# simplified_auv_power_layout_v1_0.net
KiCad netlist of a schematic drawn in EAGLE
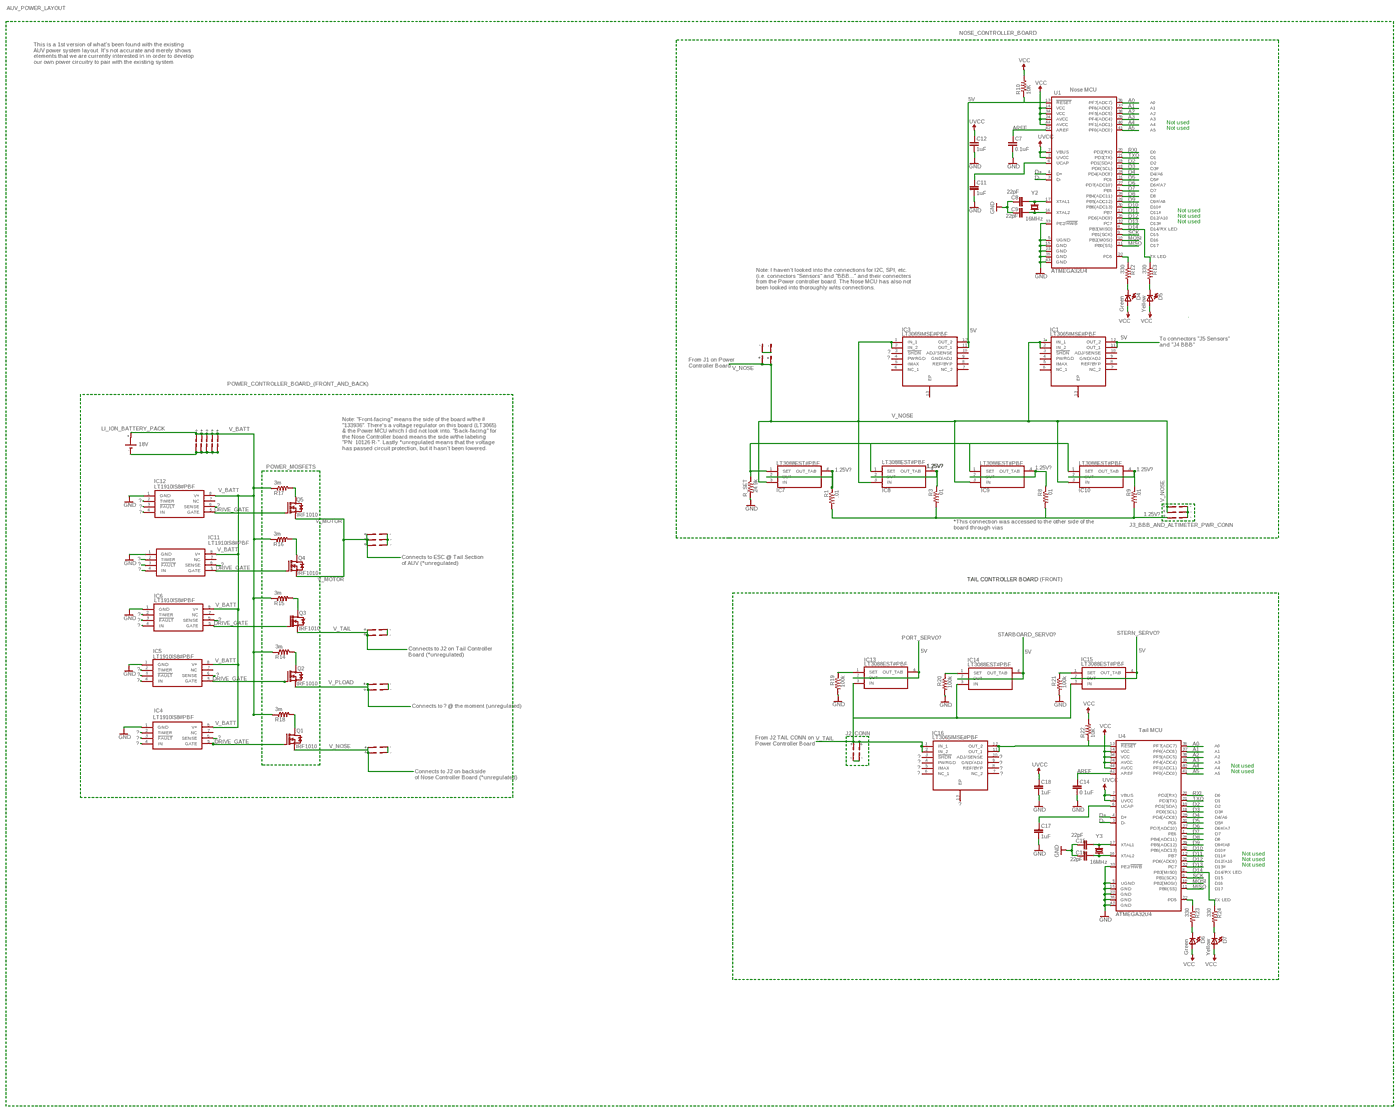
[diagram p0: schematic, sheet 1, overview]
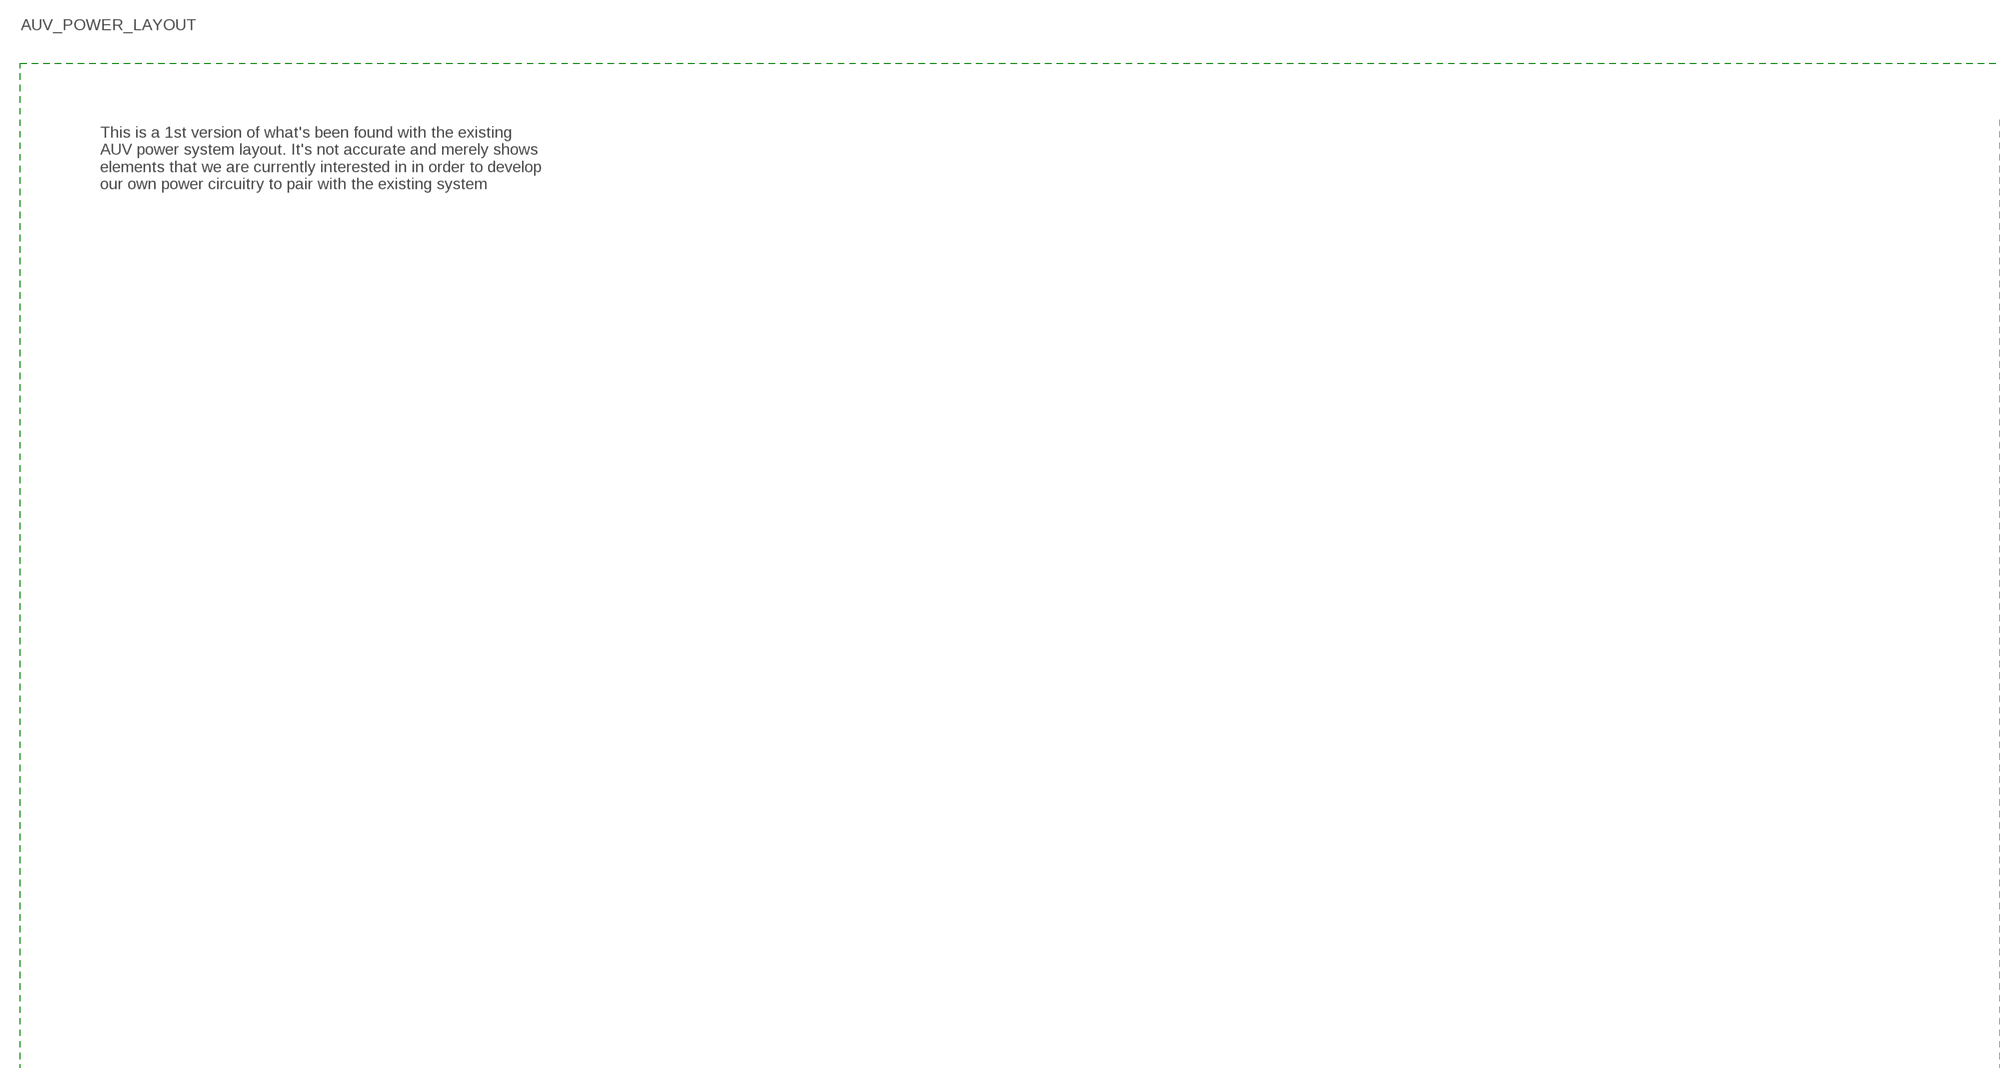
[diagram p1: schematic, sheet 1, part 1 of 4]
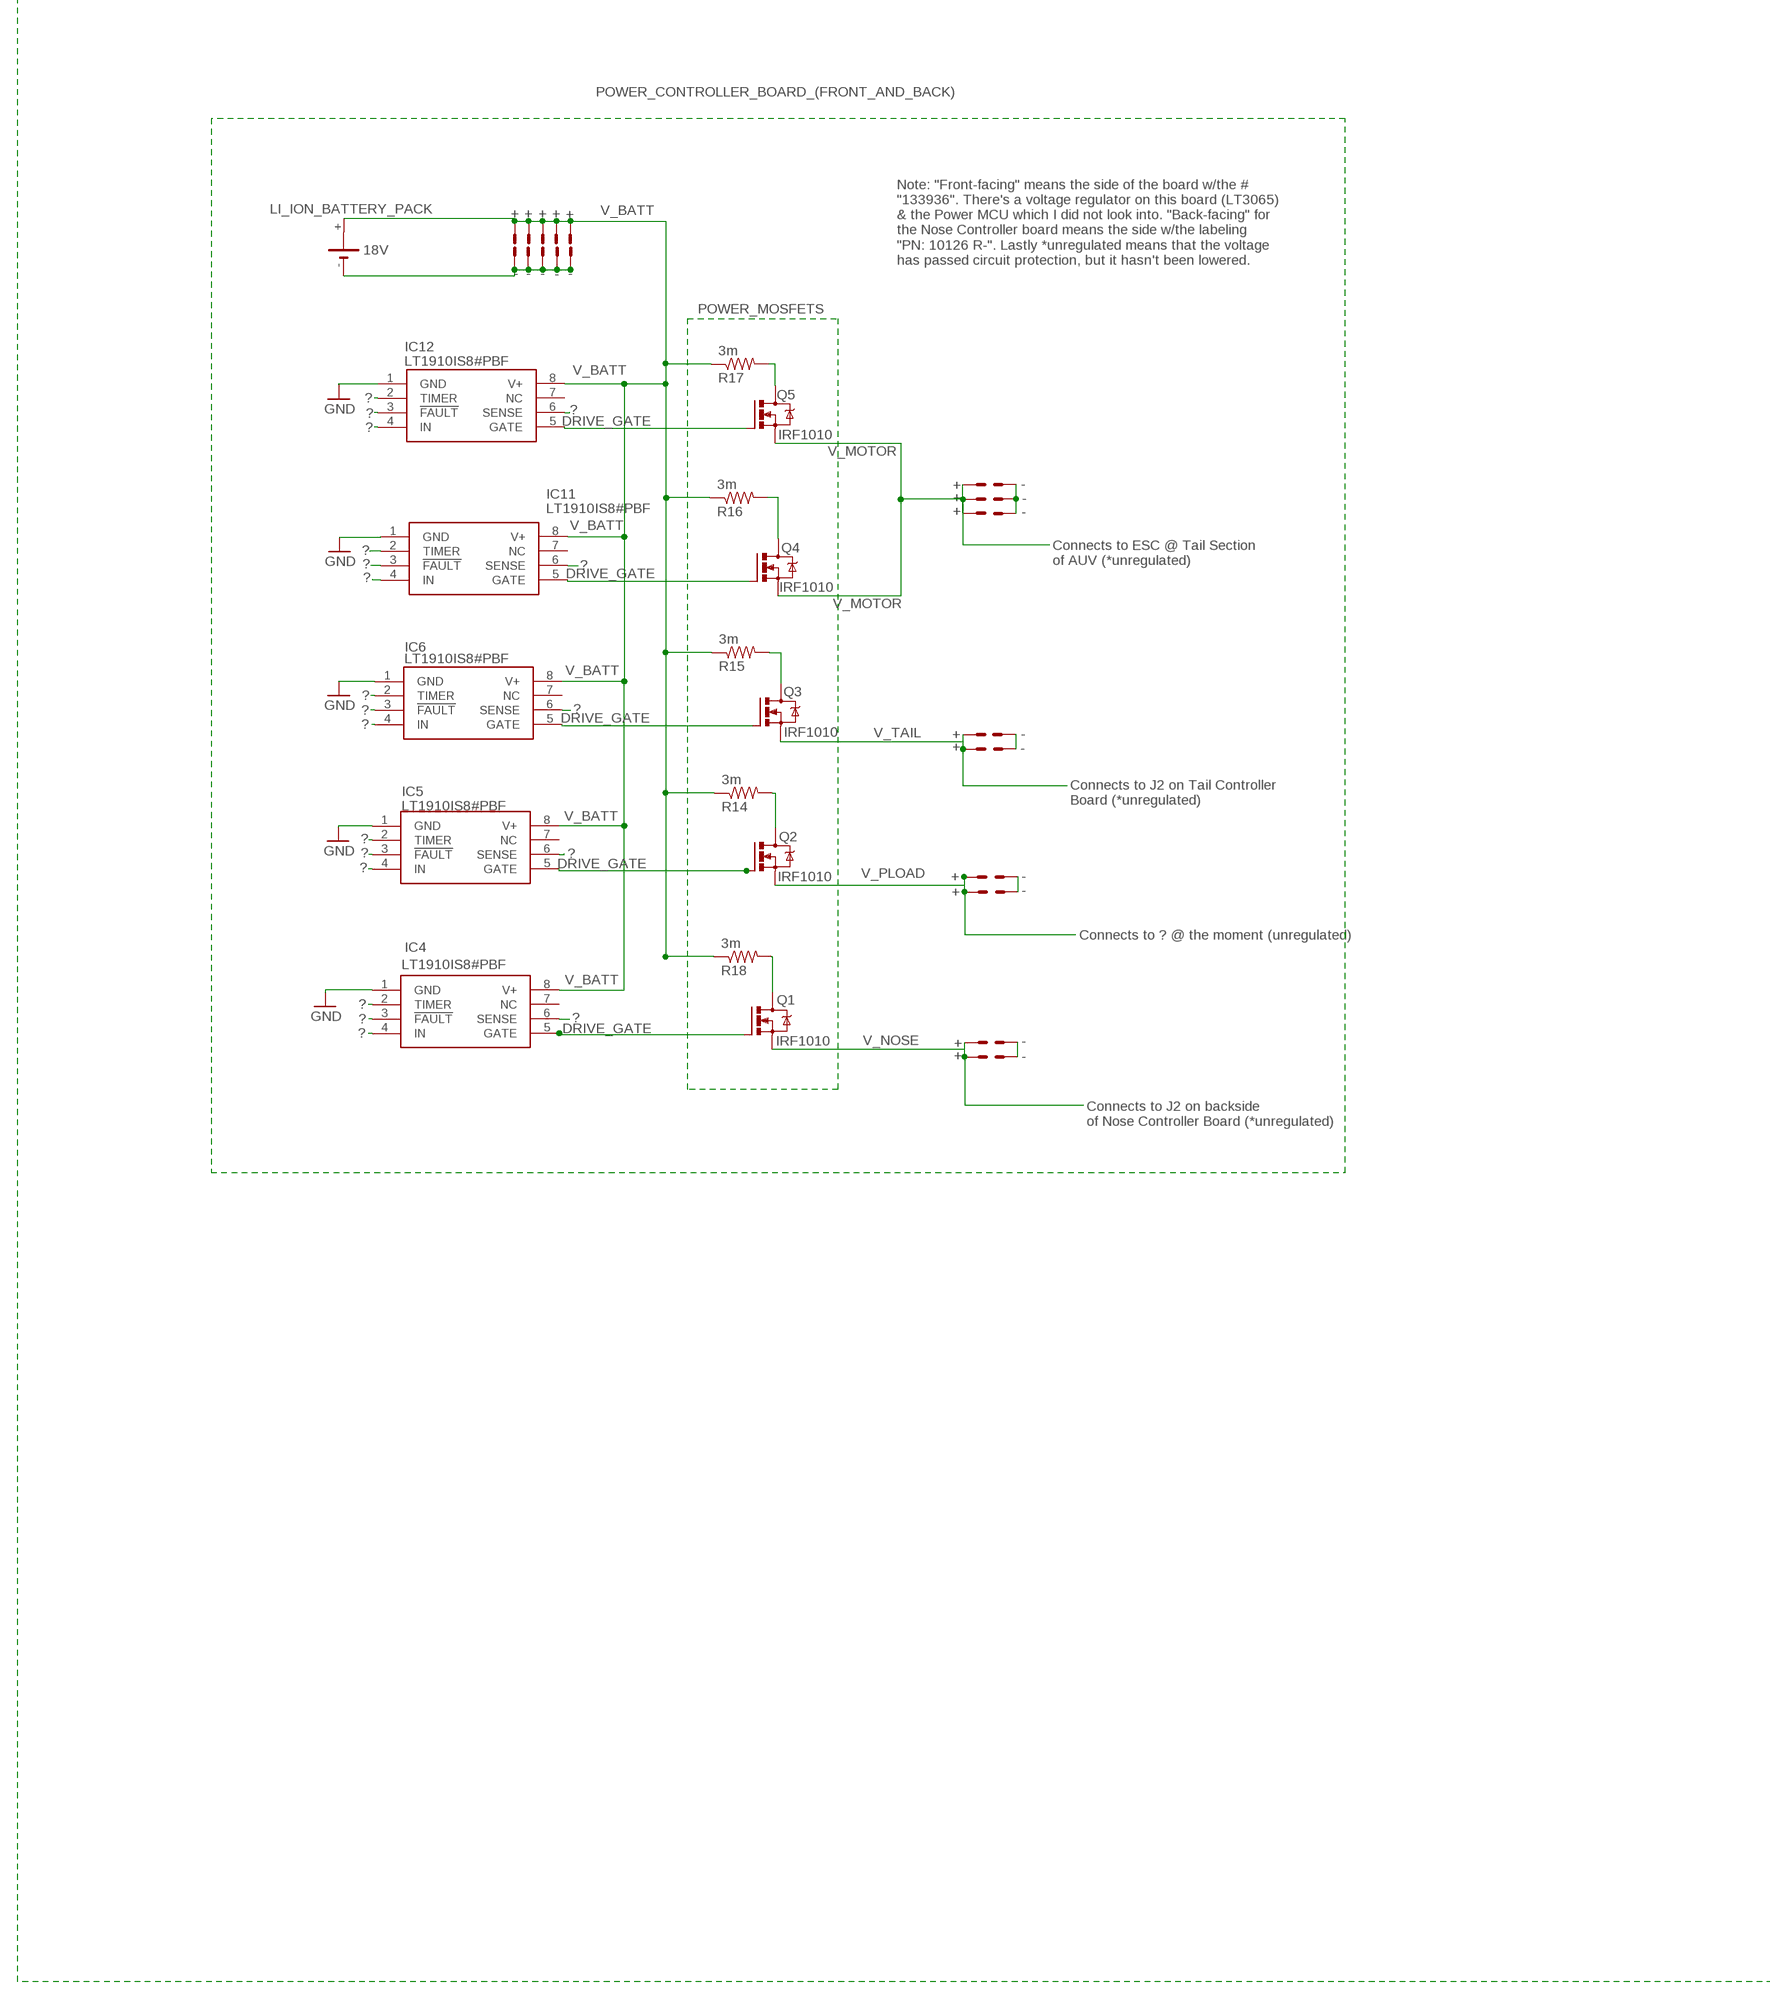
[diagram p2: schematic, sheet 1, part 2 of 4]
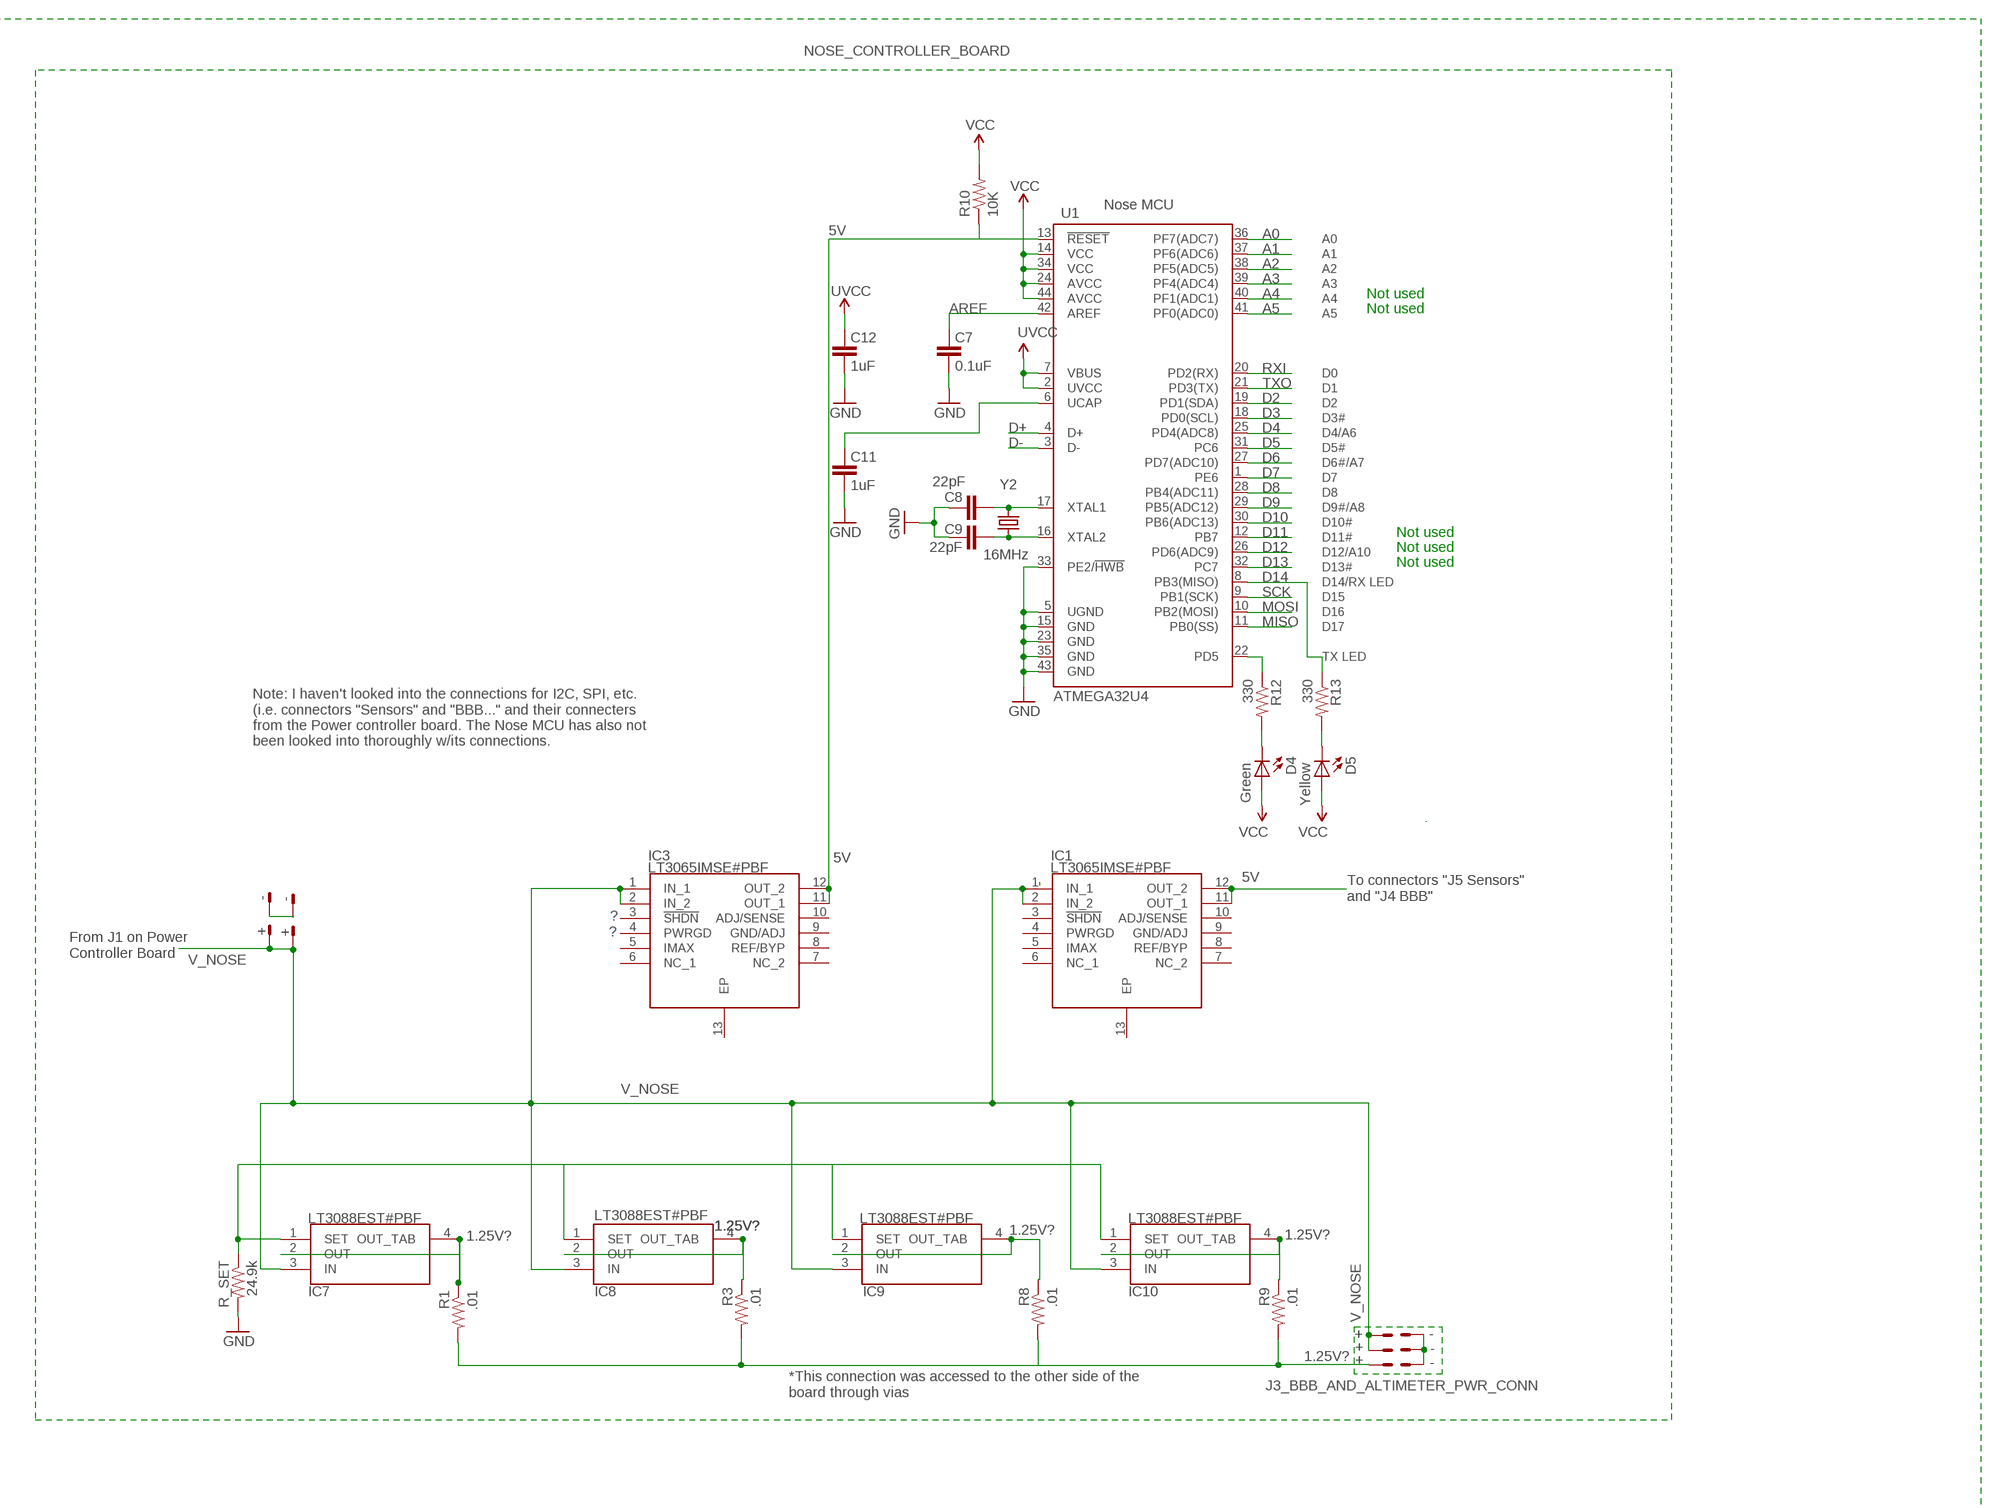
[diagram p3: schematic, sheet 1, part 3 of 4]
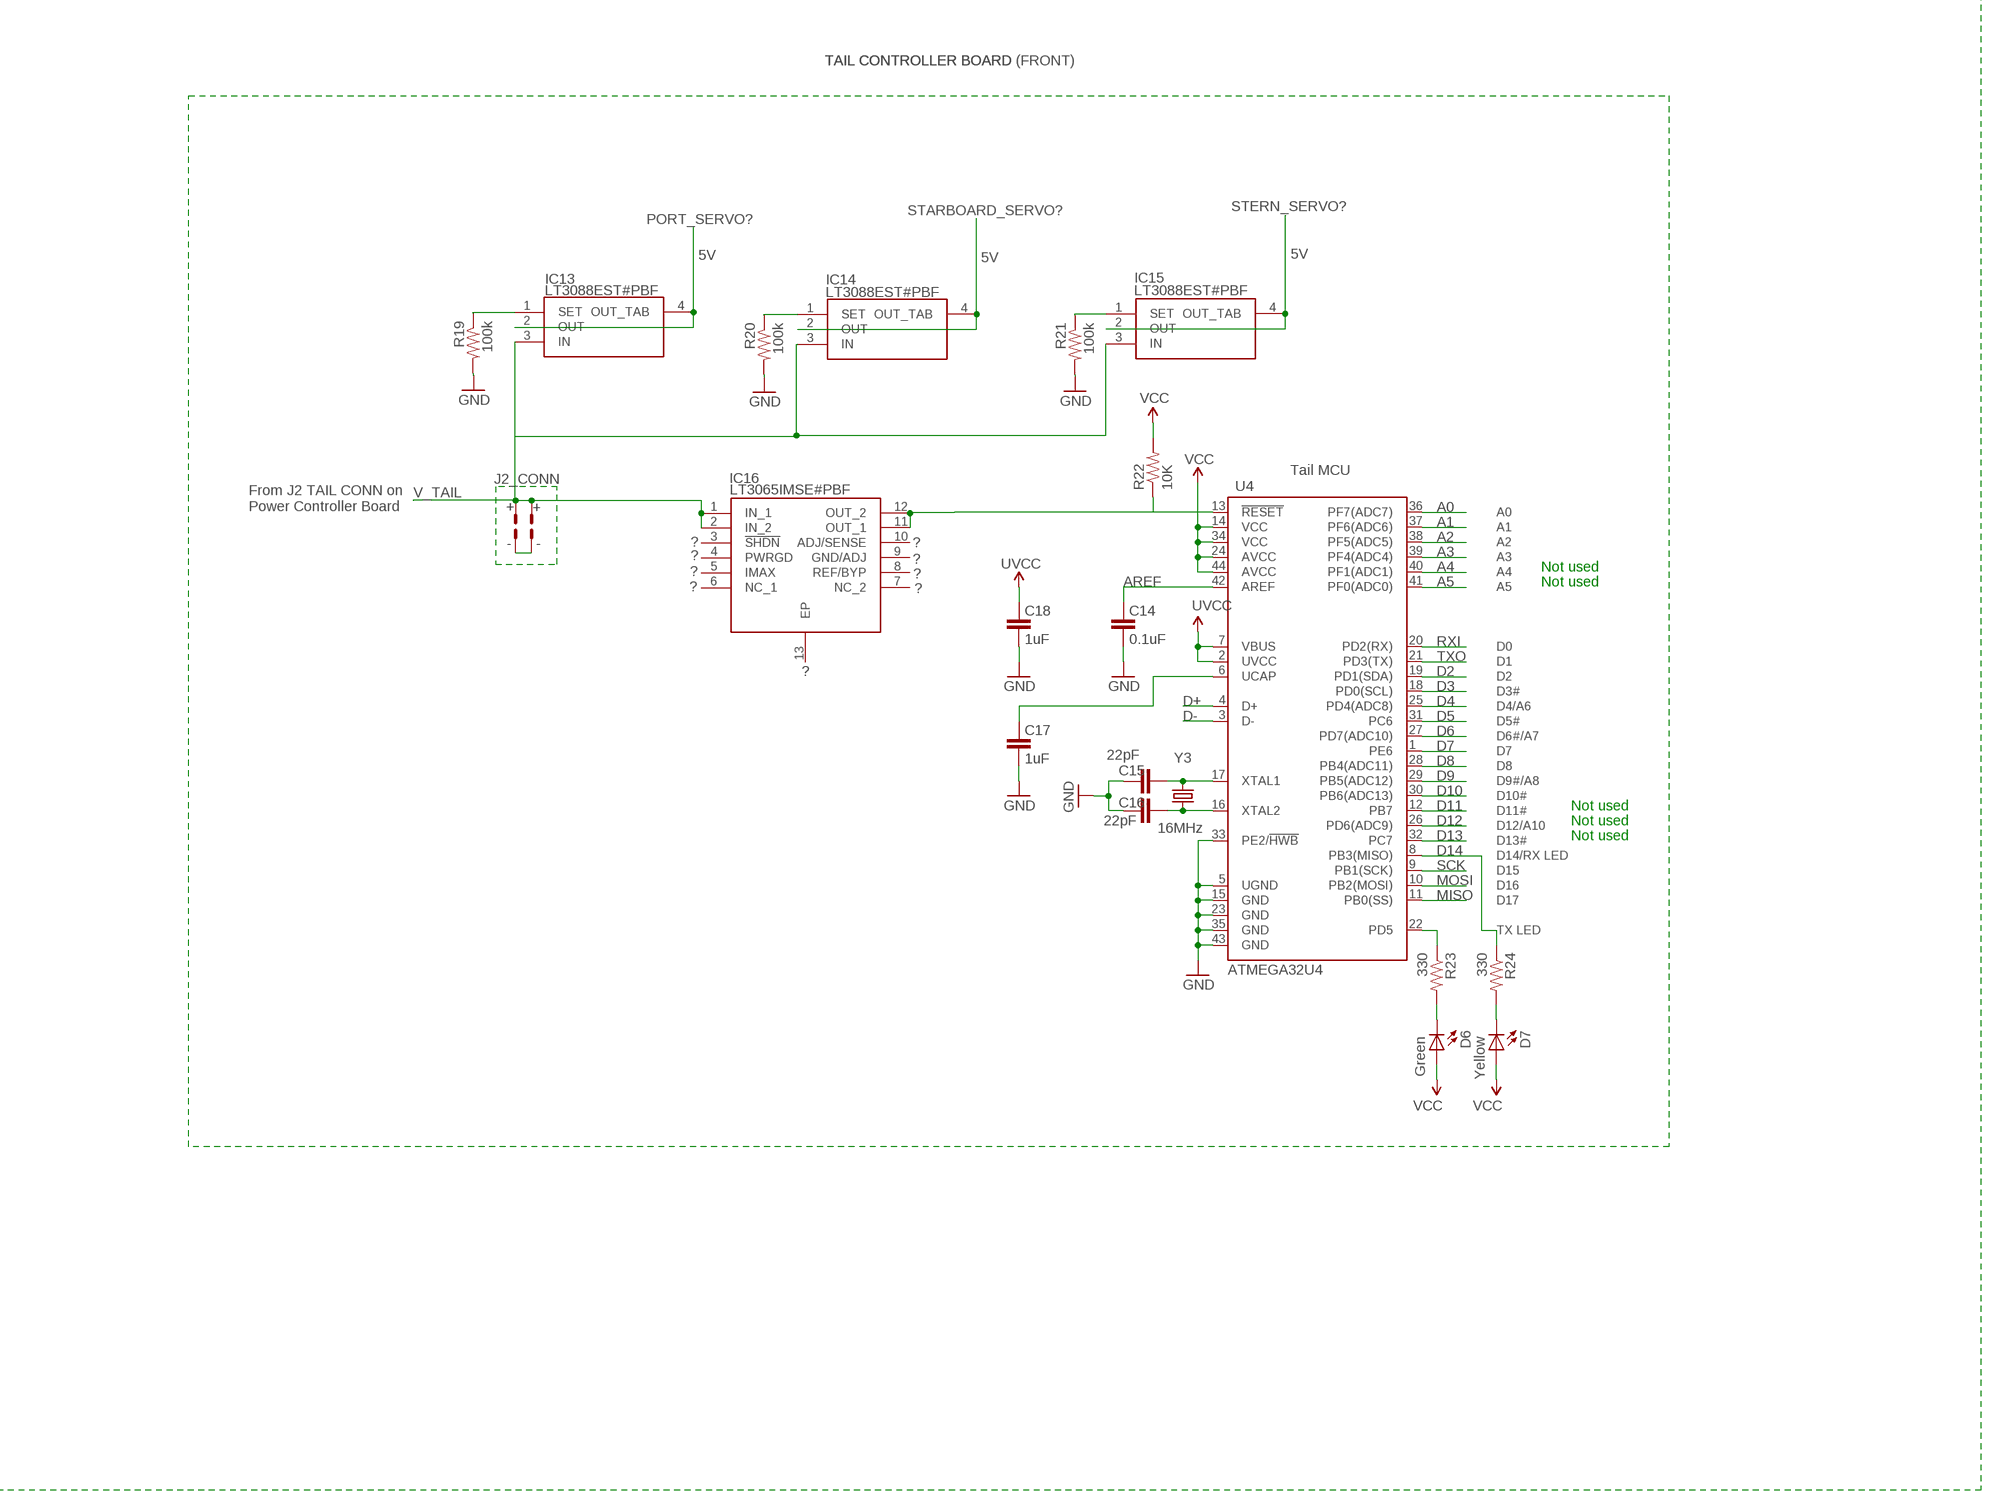
[diagram p4: schematic, sheet 1, part 4 of 4]

(export (version "E")
  (design (tool "Eeschema 10.0.6"))
  (components
    (comp (ref "C7")
      (value "0.1uF")
      (footprint "eagle-import:0603-CAP")
      (libsource (lib "eagle-import") (part "CAP0603-CAP"))
    )
    (comp (ref "C8")
      (value "22pF")
      (footprint "eagle-import:0603-CAP")
      (libsource (lib "eagle-import") (part "CAP0603-CAP"))
    )
    (comp (ref "C9")
      (value "22pF")
      (footprint "eagle-import:0603-CAP")
      (libsource (lib "eagle-import") (part "CAP0603-CAP"))
    )
    (comp (ref "C11")
      (value "1uF")
      (footprint "eagle-import:0603-CAP")
      (libsource (lib "eagle-import") (part "CAP0603-CAP"))
    )
    (comp (ref "C12")
      (value "1uF")
      (footprint "eagle-import:0603-CAP")
      (libsource (lib "eagle-import") (part "CAP0603-CAP"))
    )
    (comp (ref "C14")
      (value "0.1uF")
      (footprint "eagle-import:0603-CAP")
      (libsource (lib "eagle-import") (part "CAP0603-CAP"))
    )
    (comp (ref "C15")
      (value "22pF")
      (footprint "eagle-import:0603-CAP")
      (libsource (lib "eagle-import") (part "CAP0603-CAP"))
    )
    (comp (ref "C16")
      (value "22pF")
      (footprint "eagle-import:0603-CAP")
      (libsource (lib "eagle-import") (part "CAP0603-CAP"))
    )
    (comp (ref "C17")
      (value "1uF")
      (footprint "eagle-import:0603-CAP")
      (libsource (lib "eagle-import") (part "CAP0603-CAP"))
    )
    (comp (ref "C18")
      (value "1uF")
      (footprint "eagle-import:0603-CAP")
      (libsource (lib "eagle-import") (part "CAP0603-CAP"))
    )
    (comp (ref "D4")
      (value "Green")
      (footprint "eagle-import:LED-0603")
      (libsource (lib "eagle-import") (part "LED0603"))
    )
    (comp (ref "D5")
      (value "Yellow")
      (footprint "eagle-import:LED-0603")
      (libsource (lib "eagle-import") (part "LED0603"))
    )
    (comp (ref "D6")
      (value "Green")
      (footprint "eagle-import:LED-0603")
      (libsource (lib "eagle-import") (part "LED0603"))
    )
    (comp (ref "D7")
      (value "Yellow")
      (footprint "eagle-import:LED-0603")
      (libsource (lib "eagle-import") (part "LED0603"))
    )
    (comp (ref "IC1")
      (value "LT3065IMSE#PBF")
      (footprint "eagle-import:SOP65P490X110-13N")
      (fields (field (name "MOUSER_PART_NUMBER") "584-LT3065IMSE#PBF"))
      (libsource (lib "eagle-import") (part "LT3065IMSE#PBF"))
    )
    (comp (ref "IC3")
      (value "LT3065IMSE#PBF")
      (footprint "eagle-import:SOP65P490X110-13N")
      (fields (field (name "MOUSER_PART_NUMBER") "584-LT3065IMSE#PBF"))
      (libsource (lib "eagle-import") (part "LT3065IMSE#PBF"))
    )
    (comp (ref "IC4")
      (value "LT1910IS8#PBF")
      (footprint "eagle-import:SOIC127P599X175-8N")
      (fields
        (field (name "MOUSER_PART_NUMBER") "584-LT1910IS8#PBF")
        (field (name "RS_PART_NUMBER") "7799502")
      )
      (libsource (lib "eagle-import") (part "LT1910IS8#PBF"))
    )
    (comp (ref "IC5")
      (value "LT1910IS8#PBF")
      (footprint "eagle-import:SOIC127P599X175-8N")
      (fields
        (field (name "MOUSER_PART_NUMBER") "584-LT1910IS8#PBF")
        (field (name "RS_PART_NUMBER") "7799502")
      )
      (libsource (lib "eagle-import") (part "LT1910IS8#PBF"))
    )
    (comp (ref "IC6")
      (value "LT1910IS8#PBF")
      (footprint "eagle-import:SOIC127P599X175-8N")
      (fields
        (field (name "MOUSER_PART_NUMBER") "584-LT1910IS8#PBF")
        (field (name "RS_PART_NUMBER") "7799502")
      )
      (libsource (lib "eagle-import") (part "LT1910IS8#PBF"))
    )
    (comp (ref "IC7")
      (value "LT3088EST#PBF")
      (footprint "eagle-import:SOT230P700X180-4N")
      (fields (field (name "MOUSER_PART_NUMBER") "584-LT3088EST#PBF"))
      (libsource (lib "eagle-import") (part "LT3088EST#PBF"))
    )
    (comp (ref "IC8")
      (value "LT3088EST#PBF")
      (footprint "eagle-import:SOT230P700X180-4N")
      (fields (field (name "MOUSER_PART_NUMBER") "584-LT3088EST#PBF"))
      (libsource (lib "eagle-import") (part "LT3088EST#PBF"))
    )
    (comp (ref "IC9")
      (value "LT3088EST#PBF")
      (footprint "eagle-import:SOT230P700X180-4N")
      (fields (field (name "MOUSER_PART_NUMBER") "584-LT3088EST#PBF"))
      (libsource (lib "eagle-import") (part "LT3088EST#PBF"))
    )
    (comp (ref "IC10")
      (value "LT3088EST#PBF")
      (footprint "eagle-import:SOT230P700X180-4N")
      (fields (field (name "MOUSER_PART_NUMBER") "584-LT3088EST#PBF"))
      (libsource (lib "eagle-import") (part "LT3088EST#PBF"))
    )
    (comp (ref "IC11")
      (value "LT1910IS8#PBF")
      (footprint "eagle-import:SOIC127P599X175-8N")
      (fields
        (field (name "MOUSER_PART_NUMBER") "584-LT1910IS8#PBF")
        (field (name "RS_PART_NUMBER") "7799502")
      )
      (libsource (lib "eagle-import") (part "LT1910IS8#PBF"))
    )
    (comp (ref "IC12")
      (value "LT1910IS8#PBF")
      (footprint "eagle-import:SOIC127P599X175-8N")
      (fields
        (field (name "MOUSER_PART_NUMBER") "584-LT1910IS8#PBF")
        (field (name "RS_PART_NUMBER") "7799502")
      )
      (libsource (lib "eagle-import") (part "LT1910IS8#PBF"))
    )
    (comp (ref "IC13")
      (value "LT3088EST#PBF")
      (footprint "eagle-import:SOT230P700X180-4N")
      (fields (field (name "MOUSER_PART_NUMBER") "584-LT3088EST#PBF"))
      (libsource (lib "eagle-import") (part "LT3088EST#PBF"))
    )
    (comp (ref "IC14")
      (value "LT3088EST#PBF")
      (footprint "eagle-import:SOT230P700X180-4N")
      (fields (field (name "MOUSER_PART_NUMBER") "584-LT3088EST#PBF"))
      (libsource (lib "eagle-import") (part "LT3088EST#PBF"))
    )
    (comp (ref "IC15")
      (value "LT3088EST#PBF")
      (footprint "eagle-import:SOT230P700X180-4N")
      (fields (field (name "MOUSER_PART_NUMBER") "584-LT3088EST#PBF"))
      (libsource (lib "eagle-import") (part "LT3088EST#PBF"))
    )
    (comp (ref "IC16")
      (value "LT3065IMSE#PBF")
      (footprint "eagle-import:SOP65P490X110-13N")
      (fields (field (name "MOUSER_PART_NUMBER") "584-LT3065IMSE#PBF"))
      (libsource (lib "eagle-import") (part "LT3065IMSE#PBF"))
    )
    (comp (ref "J4_BATTERY_CONNECTOR")
      (value "J4_BATTERY")
      (footprint "eagle-import:5566-10")
      (fields (field (name "MF") "MOLEX"))
      (libsource (lib "eagle-import") (part "5566-10"))
    )
    (comp (ref "LI_ION_BATTERY_PACK")
      (value "18V")
      (footprint "eagle-import:CR2032H")
      (libsource (lib "eagle-import") (part "CR2032H"))
    )
    (comp (ref "Q1")
      (value "IRF1010")
      (footprint "eagle-import:TO220BV")
      (libsource (lib "eagle-import") (part "IRF540"))
    )
    (comp (ref "Q2")
      (value "IRF1010")
      (footprint "eagle-import:TO220BV")
      (libsource (lib "eagle-import") (part "IRF540"))
    )
    (comp (ref "Q3")
      (value "IRF1010")
      (footprint "eagle-import:TO220BV")
      (libsource (lib "eagle-import") (part "IRF540"))
    )
    (comp (ref "Q4")
      (value "IRF1010")
      (footprint "eagle-import:TO220BV")
      (libsource (lib "eagle-import") (part "IRF540"))
    )
    (comp (ref "Q5")
      (value "IRF1010")
      (footprint "eagle-import:TO220BV")
      (libsource (lib "eagle-import") (part "IRF540"))
    )
    (comp (ref "R1")
      (value ".01")
      (footprint "eagle-import:0414V")
      (libsource (lib "eagle-import") (part "R-US_0414/5V"))
    )
    (comp (ref "R3")
      (value ".01")
      (footprint "eagle-import:0414V")
      (libsource (lib "eagle-import") (part "R-US_0414/5V"))
    )
    (comp (ref "R8")
      (value ".01")
      (footprint "eagle-import:0414V")
      (libsource (lib "eagle-import") (part "R-US_0414/5V"))
    )
    (comp (ref "R9")
      (value ".01")
      (footprint "eagle-import:0414V")
      (libsource (lib "eagle-import") (part "R-US_0414/5V"))
    )
    (comp (ref "R10")
      (value "10K")
      (footprint "eagle-import:0603-RES")
      (libsource (lib "eagle-import") (part "RESISTOR0603-RES"))
    )
    (comp (ref "R12")
      (value "330")
      (footprint "eagle-import:0603-RES")
      (libsource (lib "eagle-import") (part "RESISTOR0603-RES"))
    )
    (comp (ref "R13")
      (value "330")
      (footprint "eagle-import:0603-RES")
      (libsource (lib "eagle-import") (part "RESISTOR0603-RES"))
    )
    (comp (ref "R14")
      (value "3m")
      (footprint "eagle-import:0414V")
      (libsource (lib "eagle-import") (part "R-US_0414/5V"))
    )
    (comp (ref "R15")
      (value "3m")
      (footprint "eagle-import:0414V")
      (libsource (lib "eagle-import") (part "R-US_0414/5V"))
    )
    (comp (ref "R16")
      (value "3m")
      (footprint "eagle-import:0414V")
      (libsource (lib "eagle-import") (part "R-US_0414/5V"))
    )
    (comp (ref "R17")
      (value "3m")
      (footprint "eagle-import:0414V")
      (libsource (lib "eagle-import") (part "R-US_0414/5V"))
    )
    (comp (ref "R18")
      (value "3m")
      (footprint "eagle-import:0414V")
      (libsource (lib "eagle-import") (part "R-US_0414/5V"))
    )
    (comp (ref "R19")
      (value "100k")
      (footprint "eagle-import:0414V")
      (libsource (lib "eagle-import") (part "R-US_0414/5V"))
    )
    (comp (ref "R20")
      (value "100k")
      (footprint "eagle-import:0414V")
      (libsource (lib "eagle-import") (part "R-US_0414/5V"))
    )
    (comp (ref "R21")
      (value "100k")
      (footprint "eagle-import:0414V")
      (libsource (lib "eagle-import") (part "R-US_0414/5V"))
    )
    (comp (ref "R22")
      (value "10K")
      (footprint "eagle-import:0603-RES")
      (libsource (lib "eagle-import") (part "RESISTOR0603-RES"))
    )
    (comp (ref "R23")
      (value "330")
      (footprint "eagle-import:0603-RES")
      (libsource (lib "eagle-import") (part "RESISTOR0603-RES"))
    )
    (comp (ref "R24")
      (value "330")
      (footprint "eagle-import:0603-RES")
      (libsource (lib "eagle-import") (part "RESISTOR0603-RES"))
    )
    (comp (ref "R_SET")
      (value "24.9k")
      (footprint "eagle-import:0414V")
      (libsource (lib "eagle-import") (part "R-US_0414/5V"))
    )
    (comp (ref "U1")
      (value "ATMEGA32U4")
      (footprint "eagle-import:QFN-44-NOPAD_1_1-OUTFAKES")
      (libsource (lib "eagle-import") (part "ATMEGA32U4OUTFAKES"))
    )
    (comp (ref "U4")
      (value "ATMEGA32U4")
      (footprint "eagle-import:QFN-44-NOPAD_1_1-OUTFAKES")
      (libsource (lib "eagle-import") (part "ATMEGA32U4OUTFAKES"))
    )
    (comp (ref "X3")
      (value "-")
      (footprint "eagle-import:87758-0216")
      (fields (field (name "MF") "MOLEX") (field (name "MPN") "87758-0216"))
      (libsource (lib "eagle-import") (part "87758-0216"))
    )
    (comp (ref "X4")
      (value "+")
      (footprint "eagle-import:87758-0216")
      (fields (field (name "MF") "MOLEX") (field (name "MPN") "87758-0216"))
      (libsource (lib "eagle-import") (part "87758-0216"))
    )
    (comp (ref "X6")
      (value "52746-4")
      (footprint "eagle-import:52746-4")
      (fields (field (name "MF") "MOLEX") (field (name "MPN") "52746-442"))
      (libsource (lib "eagle-import") (part "52746-4"))
    )
    (comp (ref "X7")
      (value "52746-4")
      (footprint "eagle-import:52746-4")
      (fields (field (name "MF") "MOLEX") (field (name "MPN") "52746-442"))
      (libsource (lib "eagle-import") (part "52746-4"))
    )
    (comp (ref "X8")
      (value "52746-4")
      (footprint "eagle-import:52746-4")
      (fields (field (name "MF") "MOLEX") (field (name "MPN") "52746-442"))
      (libsource (lib "eagle-import") (part "52746-4"))
    )
    (comp (ref "X9")
      (value "52746-4")
      (footprint "eagle-import:52746-4")
      (fields (field (name "MF") "MOLEX") (field (name "MPN") "52746-442"))
      (libsource (lib "eagle-import") (part "52746-4"))
    )
    (comp (ref "X10")
      (value "52746-6")
      (footprint "eagle-import:52746-6")
      (fields (field (name "MF") "MOLEX"))
      (libsource (lib "eagle-import") (part "52746-6"))
    )
    (comp (ref "X11")
      (value "52746-6")
      (footprint "eagle-import:52746-6")
      (fields (field (name "MF") "MOLEX"))
      (libsource (lib "eagle-import") (part "52746-6"))
    )
    (comp (ref "Y2")
      (value "16MHz")
      (footprint "eagle-import:CRYSTAL-SMD-5X3")
      (libsource (lib "eagle-import") (part "CRYSTAL5X3"))
    )
    (comp (ref "Y3")
      (value "16MHz")
      (footprint "eagle-import:CRYSTAL-SMD-5X3")
      (libsource (lib "eagle-import") (part "CRYSTAL5X3"))
    )
  )
  (nets
    (net (code "1") (name "/+") (class "Default")
      (node (ref "IC11") (pin "8") (pinfunction "V+_8") (pintype "bidirectional"))
      (node (ref "IC12") (pin "8") (pinfunction "V+_8") (pintype "bidirectional"))
      (node (ref "IC4") (pin "8") (pinfunction "V+_8") (pintype "bidirectional"))
      (node (ref "IC5") (pin "8") (pinfunction "V+_8") (pintype "bidirectional"))
      (node (ref "IC6") (pin "8") (pinfunction "V+_8") (pintype "bidirectional"))
      (node (ref "J4_BATTERY_CONNECTOR") (pin "1") (pinfunction "S_1") (pintype "passive"))
      (node (ref "J4_BATTERY_CONNECTOR") (pin "2") (pinfunction "S_2") (pintype "passive"))
      (node (ref "J4_BATTERY_CONNECTOR") (pin "3") (pinfunction "S_3") (pintype "passive"))
      (node (ref "J4_BATTERY_CONNECTOR") (pin "4") (pinfunction "S_4") (pintype "passive"))
      (node (ref "J4_BATTERY_CONNECTOR") (pin "5") (pinfunction "S_5") (pintype "passive"))
      (node (ref "LI_ION_BATTERY_PACK") (pin "+") (pinfunction "+_+") (pintype "passive"))
      (node (ref "R14") (pin "1") (pinfunction "1_1") (pintype "passive"))
      (node (ref "R15") (pin "1") (pinfunction "1_1") (pintype "passive"))
      (node (ref "R16") (pin "1") (pinfunction "1_1") (pintype "passive"))
      (node (ref "R17") (pin "1") (pinfunction "1_1") (pintype "passive"))
      (node (ref "R18") (pin "1") (pinfunction "1_1") (pintype "passive"))
    )
    (net (code "2") (name "/-") (class "Default")
      (node (ref "J4_BATTERY_CONNECTOR") (pin "10") (pinfunction "S_10") (pintype "passive"))
      (node (ref "J4_BATTERY_CONNECTOR") (pin "6") (pinfunction "S_6") (pintype "passive"))
      (node (ref "J4_BATTERY_CONNECTOR") (pin "7") (pinfunction "S_7") (pintype "passive"))
      (node (ref "J4_BATTERY_CONNECTOR") (pin "8") (pinfunction "S_8") (pintype "passive"))
      (node (ref "J4_BATTERY_CONNECTOR") (pin "9") (pinfunction "S_9") (pintype "passive"))
      (node (ref "LI_ION_BATTERY_PACK") (pin "-") (pinfunction "-_-") (pintype "passive"))
    )
    (net (code "3") (name "/1.25V?") (class "Default")
      (node (ref "IC10") (pin "2") (pinfunction "OUT_2") (pintype "output"))
      (node (ref "IC10") (pin "4") (pinfunction "OUT_TAB_4") (pintype "output"))
      (node (ref "IC7") (pin "2") (pinfunction "OUT_2") (pintype "output"))
      (node (ref "IC7") (pin "4") (pinfunction "OUT_TAB_4") (pintype "output"))
      (node (ref "IC8") (pin "2") (pinfunction "OUT_2") (pintype "output"))
      (node (ref "IC8") (pin "4") (pinfunction "OUT_TAB_4") (pintype "output"))
      (node (ref "IC9") (pin "2") (pinfunction "OUT_2") (pintype "output"))
      (node (ref "IC9") (pin "4") (pinfunction "OUT_TAB_4") (pintype "output"))
      (node (ref "R1") (pin "1") (pinfunction "1_1") (pintype "passive"))
      (node (ref "R3") (pin "1") (pinfunction "1_1") (pintype "passive"))
      (node (ref "R8") (pin "1") (pinfunction "1_1") (pintype "passive"))
      (node (ref "R9") (pin "1") (pinfunction "1_1") (pintype "passive"))
    )
    (net (code "4") (name "/?") (class "Default")
      (node (ref "IC11") (pin "2") (pinfunction "TIMER_2") (pintype "bidirectional"))
    )
    (net (code "5") (name "/A0") (class "Default")
      (node (ref "U1") (pin "36") (pinfunction "PF7(ADC7)_36") (pintype "bidirectional"))
      (node (ref "U4") (pin "36") (pinfunction "PF7(ADC7)_36") (pintype "bidirectional"))
    )
    (net (code "6") (name "/A1") (class "Default")
      (node (ref "U1") (pin "37") (pinfunction "PF6(ADC6)_37") (pintype "bidirectional"))
      (node (ref "U4") (pin "37") (pinfunction "PF6(ADC6)_37") (pintype "bidirectional"))
    )
    (net (code "7") (name "/A2") (class "Default")
      (node (ref "U1") (pin "38") (pinfunction "PF5(ADC5)_38") (pintype "bidirectional"))
      (node (ref "U4") (pin "38") (pinfunction "PF5(ADC5)_38") (pintype "bidirectional"))
    )
    (net (code "8") (name "/A3") (class "Default")
      (node (ref "U1") (pin "39") (pinfunction "PF4(ADC4)_39") (pintype "bidirectional"))
      (node (ref "U4") (pin "39") (pinfunction "PF4(ADC4)_39") (pintype "bidirectional"))
    )
    (net (code "9") (name "/A4") (class "Default")
      (node (ref "U1") (pin "40") (pinfunction "PF1(ADC1)_40") (pintype "bidirectional"))
      (node (ref "U4") (pin "40") (pinfunction "PF1(ADC1)_40") (pintype "bidirectional"))
    )
    (net (code "10") (name "/A5") (class "Default")
      (node (ref "U1") (pin "41") (pinfunction "PF0(ADC0)_41") (pintype "bidirectional"))
      (node (ref "U4") (pin "41") (pinfunction "PF0(ADC0)_41") (pintype "bidirectional"))
    )
    (net (code "11") (name "/AREF") (class "Default")
      (node (ref "C14") (pin "2") (pinfunction "2_2") (pintype "passive"))
      (node (ref "C7") (pin "2") (pinfunction "2_2") (pintype "passive"))
      (node (ref "U1") (pin "42") (pinfunction "AREF_42") (pintype "bidirectional"))
      (node (ref "U4") (pin "42") (pinfunction "AREF_42") (pintype "bidirectional"))
    )
    (net (code "13") (name "/D+") (class "Default")
      (node (ref "U1") (pin "4") (pinfunction "D+_4") (pintype "bidirectional"))
      (node (ref "U4") (pin "4") (pinfunction "D+_4") (pintype "bidirectional"))
    )
    (net (code "14") (name "/D-") (class "Default")
      (node (ref "U1") (pin "3") (pinfunction "D-_3") (pintype "bidirectional"))
      (node (ref "U4") (pin "3") (pinfunction "D-_3") (pintype "bidirectional"))
    )
    (net (code "15") (name "/D2") (class "Default")
      (node (ref "U1") (pin "19") (pinfunction "PD1(SDA)_19") (pintype "bidirectional"))
      (node (ref "U4") (pin "19") (pinfunction "PD1(SDA)_19") (pintype "bidirectional"))
    )
    (net (code "16") (name "/D3") (class "Default")
      (node (ref "U1") (pin "18") (pinfunction "PD0(SCL)_18") (pintype "bidirectional"))
      (node (ref "U4") (pin "18") (pinfunction "PD0(SCL)_18") (pintype "bidirectional"))
    )
    (net (code "17") (name "/D4") (class "Default")
      (node (ref "U1") (pin "25") (pinfunction "PD4(ADC8)_25") (pintype "bidirectional"))
      (node (ref "U4") (pin "25") (pinfunction "PD4(ADC8)_25") (pintype "bidirectional"))
    )
    (net (code "18") (name "/D5") (class "Default")
      (node (ref "U1") (pin "31") (pinfunction "PC6_31") (pintype "bidirectional"))
      (node (ref "U4") (pin "31") (pinfunction "PC6_31") (pintype "bidirectional"))
    )
    (net (code "19") (name "/D6") (class "Default")
      (node (ref "U1") (pin "27") (pinfunction "PD7(ADC10)_27") (pintype "bidirectional"))
      (node (ref "U4") (pin "27") (pinfunction "PD7(ADC10)_27") (pintype "bidirectional"))
    )
    (net (code "20") (name "/D7") (class "Default")
      (node (ref "U1") (pin "1") (pinfunction "PE6_1") (pintype "bidirectional"))
      (node (ref "U4") (pin "1") (pinfunction "PE6_1") (pintype "bidirectional"))
    )
    (net (code "21") (name "/D8") (class "Default")
      (node (ref "U1") (pin "28") (pinfunction "PB4(ADC11)_28") (pintype "bidirectional"))
      (node (ref "U4") (pin "28") (pinfunction "PB4(ADC11)_28") (pintype "bidirectional"))
    )
    (net (code "22") (name "/D9") (class "Default")
      (node (ref "U1") (pin "29") (pinfunction "PB5(ADC12)_29") (pintype "bidirectional"))
      (node (ref "U4") (pin "29") (pinfunction "PB5(ADC12)_29") (pintype "bidirectional"))
    )
    (net (code "23") (name "/D10") (class "Default")
      (node (ref "U1") (pin "30") (pinfunction "PB6(ADC13)_30") (pintype "bidirectional"))
      (node (ref "U4") (pin "30") (pinfunction "PB6(ADC13)_30") (pintype "bidirectional"))
    )
    (net (code "24") (name "/D11") (class "Default")
      (node (ref "U1") (pin "12") (pinfunction "PB7_12") (pintype "bidirectional"))
      (node (ref "U4") (pin "12") (pinfunction "PB7_12") (pintype "bidirectional"))
    )
    (net (code "25") (name "/D12") (class "Default")
      (node (ref "U1") (pin "26") (pinfunction "PD6(ADC9)_26") (pintype "bidirectional"))
      (node (ref "U4") (pin "26") (pinfunction "PD6(ADC9)_26") (pintype "bidirectional"))
    )
    (net (code "26") (name "/D13") (class "Default")
      (node (ref "U1") (pin "32") (pinfunction "PC7_32") (pintype "bidirectional"))
      (node (ref "U4") (pin "32") (pinfunction "PC7_32") (pintype "bidirectional"))
    )
    (net (code "27") (name "/D14") (class "Default")
      (node (ref "R13") (pin "1") (pinfunction "1_1") (pintype "passive"))
      (node (ref "R24") (pin "1") (pinfunction "1_1") (pintype "passive"))
      (node (ref "U1") (pin "8") (pinfunction "PB3(MISO)_8") (pintype "bidirectional"))
      (node (ref "U4") (pin "8") (pinfunction "PB3(MISO)_8") (pintype "bidirectional"))
    )
    (net (code "28") (name "/DRIVE_GATE") (class "Default")
      (node (ref "IC5") (pin "5") (pinfunction "GATE_5") (pintype "bidirectional"))
      (node (ref "Q2") (pin "G") (pinfunction "G_G") (pintype "passive"))
    )
    (net (code "31") (name "/MISO") (class "Default")
      (node (ref "U1") (pin "11") (pinfunction "PB0(SS)_11") (pintype "bidirectional"))
      (node (ref "U4") (pin "11") (pinfunction "PB0(SS)_11") (pintype "bidirectional"))
    )
    (net (code "32") (name "/MOSI") (class "Default")
      (node (ref "U1") (pin "10") (pinfunction "PB2(MOSI)_10") (pintype "bidirectional"))
      (node (ref "U4") (pin "10") (pinfunction "PB2(MOSI)_10") (pintype "bidirectional"))
    )
    (net (code "34") (name "/PORT_SERVO?") (class "Default")
      (node (ref "IC13") (pin "2") (pinfunction "OUT_2") (pintype "output"))
      (node (ref "IC13") (pin "4") (pinfunction "OUT_TAB_4") (pintype "output"))
    )
    (net (code "37") (name "/RXI") (class "Default")
      (node (ref "U1") (pin "20") (pinfunction "PD2(RX)_20") (pintype "bidirectional"))
      (node (ref "U4") (pin "20") (pinfunction "PD2(RX)_20") (pintype "bidirectional"))
    )
    (net (code "38") (name "/SCK") (class "Default")
      (node (ref "U1") (pin "9") (pinfunction "PB1(SCK)_9") (pintype "bidirectional"))
      (node (ref "U4") (pin "9") (pinfunction "PB1(SCK)_9") (pintype "bidirectional"))
    )
    (net (code "39") (name "/STARBOARD_SERVO?") (class "Default")
      (node (ref "IC14") (pin "2") (pinfunction "OUT_2") (pintype "output"))
      (node (ref "IC14") (pin "4") (pinfunction "OUT_TAB_4") (pintype "output"))
    )
    (net (code "40") (name "/STERN_SERVO?") (class "Default")
      (node (ref "IC15") (pin "2") (pinfunction "OUT_2") (pintype "output"))
      (node (ref "IC15") (pin "4") (pinfunction "OUT_TAB_4") (pintype "output"))
    )
    (net (code "41") (name "/TXO") (class "Default")
      (node (ref "U1") (pin "21") (pinfunction "PD3(TX)_21") (pintype "bidirectional"))
      (node (ref "U4") (pin "21") (pinfunction "PD3(TX)_21") (pintype "bidirectional"))
    )
    (net (code "42") (name "/V_MOTOR") (class "Default")
      (node (ref "Q4") (pin "S") (pinfunction "S_S") (pintype "passive"))
      (node (ref "Q5") (pin "S") (pinfunction "S_S") (pintype "passive"))
      (node (ref "X10") (pin "1") (pinfunction "S_1") (pintype "passive"))
      (node (ref "X10") (pin "2") (pinfunction "S_2") (pintype "passive"))
      (node (ref "X10") (pin "3") (pinfunction "S_3") (pintype "passive"))
    )
    (net (code "43") (name "/V_NOSE") (class "Default")
      (node (ref "IC1") (pin "1") (pinfunction "IN_1_1") (pintype "bidirectional"))
      (node (ref "IC1") (pin "2") (pinfunction "IN_2_2") (pintype "bidirectional"))
      (node (ref "IC10") (pin "3") (pinfunction "IN_3") (pintype "input"))
      (node (ref "IC3") (pin "1") (pinfunction "IN_1_1") (pintype "bidirectional"))
      (node (ref "IC3") (pin "2") (pinfunction "IN_2_2") (pintype "bidirectional"))
      (node (ref "IC7") (pin "3") (pinfunction "IN_3") (pintype "input"))
      (node (ref "IC8") (pin "3") (pinfunction "IN_3") (pintype "input"))
      (node (ref "IC9") (pin "3") (pinfunction "IN_3") (pintype "input"))
      (node (ref "Q1") (pin "S") (pinfunction "S_S") (pintype "passive"))
      (node (ref "X11") (pin "2") (pinfunction "S_2") (pintype "passive"))
      (node (ref "X11") (pin "3") (pinfunction "S_3") (pintype "passive"))
      (node (ref "X4") (pin "1") (pinfunction "S_1") (pintype "passive"))
      (node (ref "X4") (pin "2") (pinfunction "S_2") (pintype "passive"))
    )
    (net (code "44") (name "/V_PLOAD") (class "Default")
      (node (ref "Q2") (pin "S") (pinfunction "S_S") (pintype "passive"))
    )
    (net (code "45") (name "/V_TAIL") (class "Default")
      (node (ref "IC13") (pin "3") (pinfunction "IN_3") (pintype "input"))
      (node (ref "IC14") (pin "3") (pinfunction "IN_3") (pintype "input"))
      (node (ref "IC15") (pin "3") (pinfunction "IN_3") (pintype "input"))
      (node (ref "IC16") (pin "1") (pinfunction "IN_1_1") (pintype "bidirectional"))
      (node (ref "IC16") (pin "2") (pinfunction "IN_2_2") (pintype "bidirectional"))
      (node (ref "Q3") (pin "S") (pinfunction "S_S") (pintype "passive"))
      (node (ref "X9") (pin "1") (pinfunction "S_1") (pintype "passive"))
      (node (ref "X9") (pin "2") (pinfunction "S_2") (pintype "passive"))
    )
    (net (code "46") (name "GND") (class "Default")
      (node (ref "C11") (pin "1") (pinfunction "1_1") (pintype "passive"))
      (node (ref "C12") (pin "1") (pinfunction "1_1") (pintype "passive"))
      (node (ref "C14") (pin "1") (pinfunction "1_1") (pintype "passive"))
      (node (ref "C15") (pin "2") (pinfunction "2_2") (pintype "passive"))
      (node (ref "C16") (pin "2") (pinfunction "2_2") (pintype "passive"))
      (node (ref "C17") (pin "1") (pinfunction "1_1") (pintype "passive"))
      (node (ref "C18") (pin "1") (pinfunction "1_1") (pintype "passive"))
      (node (ref "C7") (pin "1") (pinfunction "1_1") (pintype "passive"))
      (node (ref "C8") (pin "2") (pinfunction "2_2") (pintype "passive"))
      (node (ref "C9") (pin "2") (pinfunction "2_2") (pintype "passive"))
      (node (ref "IC11") (pin "1") (pinfunction "GND_1") (pintype "bidirectional"))
      (node (ref "IC12") (pin "1") (pinfunction "GND_1") (pintype "bidirectional"))
      (node (ref "IC4") (pin "1") (pinfunction "GND_1") (pintype "bidirectional"))
      (node (ref "IC5") (pin "1") (pinfunction "GND_1") (pintype "bidirectional"))
      (node (ref "IC6") (pin "1") (pinfunction "GND_1") (pintype "bidirectional"))
      (node (ref "R19") (pin "2") (pinfunction "2_2") (pintype "passive"))
      (node (ref "R20") (pin "2") (pinfunction "2_2") (pintype "passive"))
      (node (ref "R21") (pin "2") (pinfunction "2_2") (pintype "passive"))
      (node (ref "R_SET") (pin "2") (pinfunction "2_2") (pintype "passive"))
      (node (ref "U1") (pin "15") (pinfunction "GND_15") (pintype "bidirectional"))
      (node (ref "U1") (pin "23") (pinfunction "GND_23") (pintype "bidirectional"))
      (node (ref "U1") (pin "33") (pinfunction "PE2/~{HWB}_33") (pintype "bidirectional"))
      (node (ref "U1") (pin "35") (pinfunction "GND_35") (pintype "bidirectional"))
      (node (ref "U1") (pin "43") (pinfunction "GND_43") (pintype "bidirectional"))
      (node (ref "U1") (pin "5") (pinfunction "UGND_5") (pintype "bidirectional"))
      (node (ref "U4") (pin "15") (pinfunction "GND_15") (pintype "bidirectional"))
      (node (ref "U4") (pin "23") (pinfunction "GND_23") (pintype "bidirectional"))
      (node (ref "U4") (pin "33") (pinfunction "PE2/~{HWB}_33") (pintype "bidirectional"))
      (node (ref "U4") (pin "35") (pinfunction "GND_35") (pintype "bidirectional"))
      (node (ref "U4") (pin "43") (pinfunction "GND_43") (pintype "bidirectional"))
      (node (ref "U4") (pin "5") (pinfunction "UGND_5") (pintype "bidirectional"))
    )
    (net (code "47") (name "Net-(D4-PadC)") (class "Default")
      (node (ref "D4") (pin "C") (pinfunction "C_C") (pintype "passive"))
      (node (ref "R12") (pin "2") (pinfunction "2_2") (pintype "passive"))
    )
    (net (code "48") (name "Net-(D5-PadC)") (class "Default")
      (node (ref "D5") (pin "C") (pinfunction "C_C") (pintype "passive"))
      (node (ref "R13") (pin "2") (pinfunction "2_2") (pintype "passive"))
    )
    (net (code "49") (name "Net-(D6-PadC)") (class "Default")
      (node (ref "D6") (pin "C") (pinfunction "C_C") (pintype "passive"))
      (node (ref "R23") (pin "2") (pinfunction "2_2") (pintype "passive"))
    )
    (net (code "50") (name "Net-(D7-PadC)") (class "Default")
      (node (ref "D7") (pin "C") (pinfunction "C_C") (pintype "passive"))
      (node (ref "R24") (pin "2") (pinfunction "2_2") (pintype "passive"))
    )
    (net (code "51") (name "Net-(IC1-OUT_1)") (class "Default")
      (node (ref "IC1") (pin "11") (pinfunction "OUT_1_11") (pintype "bidirectional"))
      (node (ref "IC1") (pin "12") (pinfunction "OUT_2_12") (pintype "bidirectional"))
    )
    (net (code "52") (name "Net-(IC3-OUT_1)") (class "Default")
      (node (ref "IC3") (pin "11") (pinfunction "OUT_1_11") (pintype "bidirectional"))
      (node (ref "IC3") (pin "12") (pinfunction "OUT_2_12") (pintype "bidirectional"))
    )
    (net (code "53") (name "Net-(IC4-GATE)") (class "Default")
      (node (ref "IC4") (pin "5") (pinfunction "GATE_5") (pintype "bidirectional"))
      (node (ref "Q1") (pin "G") (pinfunction "G_G") (pintype "passive"))
    )
    (net (code "54") (name "Net-(IC6-GATE)") (class "Default")
      (node (ref "IC6") (pin "5") (pinfunction "GATE_5") (pintype "bidirectional"))
      (node (ref "Q3") (pin "G") (pinfunction "G_G") (pintype "passive"))
    )
    (net (code "55") (name "Net-(IC10-SET)") (class "Default")
      (node (ref "IC10") (pin "1") (pinfunction "SET_1") (pintype "bidirectional"))
      (node (ref "IC7") (pin "1") (pinfunction "SET_1") (pintype "bidirectional"))
      (node (ref "IC8") (pin "1") (pinfunction "SET_1") (pintype "bidirectional"))
      (node (ref "IC9") (pin "1") (pinfunction "SET_1") (pintype "bidirectional"))
      (node (ref "R_SET") (pin "1") (pinfunction "1_1") (pintype "passive"))
    )
    (net (code "56") (name "Net-(IC11-GATE)") (class "Default")
      (node (ref "IC11") (pin "5") (pinfunction "GATE_5") (pintype "bidirectional"))
      (node (ref "Q4") (pin "G") (pinfunction "G_G") (pintype "passive"))
    )
    (net (code "57") (name "Net-(IC12-GATE)") (class "Default")
      (node (ref "IC12") (pin "5") (pinfunction "GATE_5") (pintype "bidirectional"))
      (node (ref "Q5") (pin "G") (pinfunction "G_G") (pintype "passive"))
    )
    (net (code "58") (name "Net-(IC13-SET)") (class "Default")
      (node (ref "IC13") (pin "1") (pinfunction "SET_1") (pintype "bidirectional"))
      (node (ref "R19") (pin "1") (pinfunction "1_1") (pintype "passive"))
    )
    (net (code "59") (name "Net-(IC14-SET)") (class "Default")
      (node (ref "IC14") (pin "1") (pinfunction "SET_1") (pintype "bidirectional"))
      (node (ref "R20") (pin "1") (pinfunction "1_1") (pintype "passive"))
    )
    (net (code "60") (name "Net-(IC15-SET)") (class "Default")
      (node (ref "IC15") (pin "1") (pinfunction "SET_1") (pintype "bidirectional"))
      (node (ref "R21") (pin "1") (pinfunction "1_1") (pintype "passive"))
    )
    (net (code "61") (name "Net-(IC16-OUT_1)") (class "Default")
      (node (ref "IC16") (pin "11") (pinfunction "OUT_1_11") (pintype "bidirectional"))
      (node (ref "IC16") (pin "12") (pinfunction "OUT_2_12") (pintype "bidirectional"))
    )
    (net (code "62") (name "Net-(Q1-PadD)") (class "Default")
      (node (ref "Q1") (pin "D") (pinfunction "D_D") (pintype "passive"))
      (node (ref "R18") (pin "2") (pinfunction "2_2") (pintype "passive"))
    )
    (net (code "63") (name "Net-(Q2-PadD)") (class "Default")
      (node (ref "Q2") (pin "D") (pinfunction "D_D") (pintype "passive"))
      (node (ref "R14") (pin "2") (pinfunction "2_2") (pintype "passive"))
    )
    (net (code "64") (name "Net-(Q3-PadD)") (class "Default")
      (node (ref "Q3") (pin "D") (pinfunction "D_D") (pintype "passive"))
      (node (ref "R15") (pin "2") (pinfunction "2_2") (pintype "passive"))
    )
    (net (code "65") (name "Net-(Q4-PadD)") (class "Default")
      (node (ref "Q4") (pin "D") (pinfunction "D_D") (pintype "passive"))
      (node (ref "R16") (pin "2") (pinfunction "2_2") (pintype "passive"))
    )
    (net (code "66") (name "Net-(Q5-PadD)") (class "Default")
      (node (ref "Q5") (pin "D") (pinfunction "D_D") (pintype "passive"))
      (node (ref "R17") (pin "2") (pinfunction "2_2") (pintype "passive"))
    )
    (net (code "67") (name "Net-(U1-PD5)") (class "Default")
      (node (ref "R12") (pin "1") (pinfunction "1_1") (pintype "passive"))
      (node (ref "U1") (pin "22") (pinfunction "PD5_22") (pintype "bidirectional"))
    )
    (net (code "68") (name "Net-(U1-UCAP)") (class "Default")
      (node (ref "C11") (pin "2") (pinfunction "2_2") (pintype "passive"))
      (node (ref "U1") (pin "6") (pinfunction "UCAP_6") (pintype "bidirectional"))
    )
    (net (code "69") (name "Net-(U1-XTAL1)") (class "Default")
      (node (ref "C8") (pin "1") (pinfunction "1_1") (pintype "passive"))
      (node (ref "U1") (pin "17") (pinfunction "XTAL1_17") (pintype "bidirectional"))
      (node (ref "Y2") (pin "3") (pinfunction "2_3") (pintype "passive"))
    )
    (net (code "70") (name "Net-(U1-XTAL2)") (class "Default")
      (node (ref "C9") (pin "1") (pinfunction "1_1") (pintype "passive"))
      (node (ref "U1") (pin "16") (pinfunction "XTAL2_16") (pintype "bidirectional"))
      (node (ref "Y2") (pin "1") (pinfunction "1_1") (pintype "passive"))
    )
    (net (code "71") (name "Net-(U1-~{RESET})") (class "Default")
      (node (ref "R10") (pin "1") (pinfunction "1_1") (pintype "passive"))
      (node (ref "U1") (pin "13") (pinfunction "~{RESET}_13") (pintype "bidirectional"))
    )
    (net (code "72") (name "Net-(U4-PD5)") (class "Default")
      (node (ref "R23") (pin "1") (pinfunction "1_1") (pintype "passive"))
      (node (ref "U4") (pin "22") (pinfunction "PD5_22") (pintype "bidirectional"))
    )
    (net (code "73") (name "Net-(U4-UCAP)") (class "Default")
      (node (ref "C17") (pin "2") (pinfunction "2_2") (pintype "passive"))
      (node (ref "U4") (pin "6") (pinfunction "UCAP_6") (pintype "bidirectional"))
    )
    (net (code "74") (name "Net-(U4-XTAL1)") (class "Default")
      (node (ref "C15") (pin "1") (pinfunction "1_1") (pintype "passive"))
      (node (ref "U4") (pin "17") (pinfunction "XTAL1_17") (pintype "bidirectional"))
      (node (ref "Y3") (pin "3") (pinfunction "2_3") (pintype "passive"))
    )
    (net (code "75") (name "Net-(U4-XTAL2)") (class "Default")
      (node (ref "C16") (pin "1") (pinfunction "1_1") (pintype "passive"))
      (node (ref "U4") (pin "16") (pinfunction "XTAL2_16") (pintype "bidirectional"))
      (node (ref "Y3") (pin "1") (pinfunction "1_1") (pintype "passive"))
    )
    (net (code "76") (name "Net-(U4-~{RESET})") (class "Default")
      (node (ref "R22") (pin "1") (pinfunction "1_1") (pintype "passive"))
      (node (ref "U4") (pin "13") (pinfunction "~{RESET}_13") (pintype "bidirectional"))
    )
    (net (code "77") (name "Net-(X3A-S)") (class "Default")
      (node (ref "X3") (pin "1") (pinfunction "S_1") (pintype "passive"))
      (node (ref "X3") (pin "2") (pinfunction "S_2") (pintype "passive"))
    )
    (net (code "78") (name "Net-(X6A-S)") (class "Default")
      (node (ref "X6") (pin "1") (pinfunction "S_1") (pintype "passive"))
      (node (ref "X6") (pin "2") (pinfunction "S_2") (pintype "passive"))
    )
    (net (code "79") (name "Net-(X6C-S)") (class "Default")
      (node (ref "X6") (pin "3") (pinfunction "S_3") (pintype "passive"))
      (node (ref "X6") (pin "4") (pinfunction "S_4") (pintype "passive"))
    )
    (net (code "80") (name "Net-(X7A-S)") (class "Default")
      (node (ref "X7") (pin "1") (pinfunction "S_1") (pintype "passive"))
      (node (ref "X7") (pin "2") (pinfunction "S_2") (pintype "passive"))
    )
    (net (code "81") (name "Net-(X7C-S)") (class "Default")
      (node (ref "X7") (pin "3") (pinfunction "S_3") (pintype "passive"))
      (node (ref "X7") (pin "4") (pinfunction "S_4") (pintype "passive"))
    )
    (net (code "82") (name "Net-(X8A-S)") (class "Default")
      (node (ref "X8") (pin "1") (pinfunction "S_1") (pintype "passive"))
      (node (ref "X8") (pin "2") (pinfunction "S_2") (pintype "passive"))
    )
    (net (code "83") (name "Net-(X8C-S)") (class "Default")
      (node (ref "X8") (pin "3") (pinfunction "S_3") (pintype "passive"))
      (node (ref "X8") (pin "4") (pinfunction "S_4") (pintype "passive"))
    )
    (net (code "84") (name "Net-(X9C-S)") (class "Default")
      (node (ref "X9") (pin "3") (pinfunction "S_3") (pintype "passive"))
      (node (ref "X9") (pin "4") (pinfunction "S_4") (pintype "passive"))
    )
    (net (code "85") (name "Net-(X10D-S)") (class "Default")
      (node (ref "X10") (pin "4") (pinfunction "S_4") (pintype "passive"))
      (node (ref "X10") (pin "5") (pinfunction "S_5") (pintype "passive"))
      (node (ref "X10") (pin "6") (pinfunction "S_6") (pintype "passive"))
    )
    (net (code "86") (name "Net-(X11A-S)") (class "Default")
      (node (ref "R1") (pin "2") (pinfunction "2_2") (pintype "passive"))
      (node (ref "R3") (pin "2") (pinfunction "2_2") (pintype "passive"))
      (node (ref "R8") (pin "2") (pinfunction "2_2") (pintype "passive"))
      (node (ref "R9") (pin "2") (pinfunction "2_2") (pintype "passive"))
      (node (ref "X11") (pin "1") (pinfunction "S_1") (pintype "passive"))
    )
    (net (code "87") (name "Net-(X11D-S)") (class "Default")
      (node (ref "X11") (pin "4") (pinfunction "S_4") (pintype "passive"))
      (node (ref "X11") (pin "5") (pinfunction "S_5") (pintype "passive"))
      (node (ref "X11") (pin "6") (pinfunction "S_6") (pintype "passive"))
    )
    (net (code "88") (name "UVCC") (class "Default")
      (node (ref "C12") (pin "2") (pinfunction "2_2") (pintype "passive"))
      (node (ref "C18") (pin "2") (pinfunction "2_2") (pintype "passive"))
      (node (ref "U1") (pin "2") (pinfunction "UVCC_2") (pintype "bidirectional"))
      (node (ref "U1") (pin "7") (pinfunction "VBUS_7") (pintype "bidirectional"))
      (node (ref "U4") (pin "2") (pinfunction "UVCC_2") (pintype "bidirectional"))
      (node (ref "U4") (pin "7") (pinfunction "VBUS_7") (pintype "bidirectional"))
    )
    (net (code "89") (name "VCC") (class "Default")
      (node (ref "D4") (pin "A") (pinfunction "A_A") (pintype "passive"))
      (node (ref "D5") (pin "A") (pinfunction "A_A") (pintype "passive"))
      (node (ref "D6") (pin "A") (pinfunction "A_A") (pintype "passive"))
      (node (ref "D7") (pin "A") (pinfunction "A_A") (pintype "passive"))
      (node (ref "R10") (pin "2") (pinfunction "2_2") (pintype "passive"))
      (node (ref "R22") (pin "2") (pinfunction "2_2") (pintype "passive"))
      (node (ref "U1") (pin "14") (pinfunction "VCC_14") (pintype "bidirectional"))
      (node (ref "U1") (pin "24") (pinfunction "AVCC_24") (pintype "bidirectional"))
      (node (ref "U1") (pin "34") (pinfunction "VCC_34") (pintype "bidirectional"))
      (node (ref "U1") (pin "44") (pinfunction "AVCC_44") (pintype "bidirectional"))
      (node (ref "U4") (pin "14") (pinfunction "VCC_14") (pintype "bidirectional"))
      (node (ref "U4") (pin "24") (pinfunction "AVCC_24") (pintype "bidirectional"))
      (node (ref "U4") (pin "34") (pinfunction "VCC_34") (pintype "bidirectional"))
      (node (ref "U4") (pin "44") (pinfunction "AVCC_44") (pintype "bidirectional"))
    )
    (net (code "90") (name "unconnected-(IC1-ADJ{slash}SENSE-Pad10)") (class "Default")
      (node (ref "IC1") (pin "10") (pinfunction "ADJ/SENSE_10") (pintype "bidirectional"))
    )
    (net (code "91") (name "unconnected-(IC1-EP-Pad13)") (class "Default")
      (node (ref "IC1") (pin "13") (pinfunction "EP_13") (pintype "bidirectional"))
    )
    (net (code "92") (name "unconnected-(IC1-GND{slash}ADJ-Pad9)") (class "Default")
      (node (ref "IC1") (pin "9") (pinfunction "GND/ADJ_9") (pintype "bidirectional"))
    )
    (net (code "93") (name "unconnected-(IC1-IMAX-Pad5)") (class "Default")
      (node (ref "IC1") (pin "5") (pinfunction "IMAX_5") (pintype "bidirectional"))
    )
    (net (code "94") (name "unconnected-(IC1-NC_1-Pad6)") (class "Default")
      (node (ref "IC1") (pin "6") (pinfunction "NC_1_6") (pintype "bidirectional"))
    )
    (net (code "95") (name "unconnected-(IC1-NC_2-Pad7)") (class "Default")
      (node (ref "IC1") (pin "7") (pinfunction "NC_2_7") (pintype "bidirectional"))
    )
    (net (code "96") (name "unconnected-(IC1-PWRGD-Pad4)") (class "Default")
      (node (ref "IC1") (pin "4") (pinfunction "PWRGD_4") (pintype "bidirectional"))
    )
    (net (code "97") (name "unconnected-(IC1-REF{slash}BYP-Pad8)") (class "Default")
      (node (ref "IC1") (pin "8") (pinfunction "REF/BYP_8") (pintype "bidirectional"))
    )
    (net (code "98") (name "unconnected-(IC1-~{SHDN}-Pad3)") (class "Default")
      (node (ref "IC1") (pin "3") (pinfunction "~{SHDN}_3") (pintype "bidirectional"))
    )
    (net (code "99") (name "unconnected-(IC3-ADJ{slash}SENSE-Pad10)") (class "Default")
      (node (ref "IC3") (pin "10") (pinfunction "ADJ/SENSE_10") (pintype "bidirectional"))
    )
    (net (code "100") (name "unconnected-(IC3-EP-Pad13)") (class "Default")
      (node (ref "IC3") (pin "13") (pinfunction "EP_13") (pintype "bidirectional"))
    )
    (net (code "101") (name "unconnected-(IC3-GND{slash}ADJ-Pad9)") (class "Default")
      (node (ref "IC3") (pin "9") (pinfunction "GND/ADJ_9") (pintype "bidirectional"))
    )
    (net (code "102") (name "unconnected-(IC3-IMAX-Pad5)") (class "Default")
      (node (ref "IC3") (pin "5") (pinfunction "IMAX_5") (pintype "bidirectional"))
    )
    (net (code "103") (name "unconnected-(IC3-NC_1-Pad6)") (class "Default")
      (node (ref "IC3") (pin "6") (pinfunction "NC_1_6") (pintype "bidirectional"))
    )
    (net (code "104") (name "unconnected-(IC3-NC_2-Pad7)") (class "Default")
      (node (ref "IC3") (pin "7") (pinfunction "NC_2_7") (pintype "bidirectional"))
    )
    (net (code "105") (name "unconnected-(IC3-PWRGD-Pad4)") (class "Default")
      (node (ref "IC3") (pin "4") (pinfunction "PWRGD_4") (pintype "bidirectional"))
    )
    (net (code "106") (name "unconnected-(IC3-REF{slash}BYP-Pad8)") (class "Default")
      (node (ref "IC3") (pin "8") (pinfunction "REF/BYP_8") (pintype "bidirectional"))
    )
    (net (code "107") (name "unconnected-(IC3-~{SHDN}-Pad3)") (class "Default")
      (node (ref "IC3") (pin "3") (pinfunction "~{SHDN}_3") (pintype "bidirectional"))
    )
    (net (code "108") (name "unconnected-(IC4-IN-Pad4)") (class "Default")
      (node (ref "IC4") (pin "4") (pinfunction "IN_4") (pintype "bidirectional"))
    )
    (net (code "109") (name "unconnected-(IC4-NC-Pad7)") (class "Default")
      (node (ref "IC4") (pin "7") (pinfunction "NC_7") (pintype "no_connect"))
    )
    (net (code "110") (name "unconnected-(IC4-SENSE-Pad6)") (class "Default")
      (node (ref "IC4") (pin "6") (pinfunction "SENSE_6") (pintype "bidirectional"))
    )
    (net (code "111") (name "unconnected-(IC4-TIMER-Pad2)") (class "Default")
      (node (ref "IC4") (pin "2") (pinfunction "TIMER_2") (pintype "bidirectional"))
    )
    (net (code "112") (name "unconnected-(IC4-~{FAULT}-Pad3)") (class "Default")
      (node (ref "IC4") (pin "3") (pinfunction "~{FAULT}_3") (pintype "bidirectional"))
    )
    (net (code "113") (name "unconnected-(IC5-IN-Pad4)") (class "Default")
      (node (ref "IC5") (pin "4") (pinfunction "IN_4") (pintype "bidirectional"))
    )
    (net (code "114") (name "unconnected-(IC5-NC-Pad7)") (class "Default")
      (node (ref "IC5") (pin "7") (pinfunction "NC_7") (pintype "no_connect"))
    )
    (net (code "115") (name "unconnected-(IC5-SENSE-Pad6)") (class "Default")
      (node (ref "IC5") (pin "6") (pinfunction "SENSE_6") (pintype "bidirectional"))
    )
    (net (code "116") (name "unconnected-(IC5-TIMER-Pad2)") (class "Default")
      (node (ref "IC5") (pin "2") (pinfunction "TIMER_2") (pintype "bidirectional"))
    )
    (net (code "117") (name "unconnected-(IC5-~{FAULT}-Pad3)") (class "Default")
      (node (ref "IC5") (pin "3") (pinfunction "~{FAULT}_3") (pintype "bidirectional"))
    )
    (net (code "118") (name "unconnected-(IC6-IN-Pad4)") (class "Default")
      (node (ref "IC6") (pin "4") (pinfunction "IN_4") (pintype "bidirectional"))
    )
    (net (code "119") (name "unconnected-(IC6-NC-Pad7)") (class "Default")
      (node (ref "IC6") (pin "7") (pinfunction "NC_7") (pintype "no_connect"))
    )
    (net (code "120") (name "unconnected-(IC6-SENSE-Pad6)") (class "Default")
      (node (ref "IC6") (pin "6") (pinfunction "SENSE_6") (pintype "bidirectional"))
    )
    (net (code "121") (name "unconnected-(IC6-TIMER-Pad2)") (class "Default")
      (node (ref "IC6") (pin "2") (pinfunction "TIMER_2") (pintype "bidirectional"))
    )
    (net (code "122") (name "unconnected-(IC6-~{FAULT}-Pad3)") (class "Default")
      (node (ref "IC6") (pin "3") (pinfunction "~{FAULT}_3") (pintype "bidirectional"))
    )
    (net (code "123") (name "unconnected-(IC11-IN-Pad4)") (class "Default")
      (node (ref "IC11") (pin "4") (pinfunction "IN_4") (pintype "bidirectional"))
    )
    (net (code "124") (name "unconnected-(IC11-NC-Pad7)") (class "Default")
      (node (ref "IC11") (pin "7") (pinfunction "NC_7") (pintype "no_connect"))
    )
    (net (code "125") (name "unconnected-(IC11-SENSE-Pad6)") (class "Default")
      (node (ref "IC11") (pin "6") (pinfunction "SENSE_6") (pintype "bidirectional"))
    )
    (net (code "126") (name "unconnected-(IC11-~{FAULT}-Pad3)") (class "Default")
      (node (ref "IC11") (pin "3") (pinfunction "~{FAULT}_3") (pintype "bidirectional"))
    )
    (net (code "127") (name "unconnected-(IC12-IN-Pad4)") (class "Default")
      (node (ref "IC12") (pin "4") (pinfunction "IN_4") (pintype "bidirectional"))
    )
    (net (code "128") (name "unconnected-(IC12-NC-Pad7)") (class "Default")
      (node (ref "IC12") (pin "7") (pinfunction "NC_7") (pintype "no_connect"))
    )
    (net (code "129") (name "unconnected-(IC12-SENSE-Pad6)") (class "Default")
      (node (ref "IC12") (pin "6") (pinfunction "SENSE_6") (pintype "bidirectional"))
    )
    (net (code "130") (name "unconnected-(IC12-TIMER-Pad2)") (class "Default")
      (node (ref "IC12") (pin "2") (pinfunction "TIMER_2") (pintype "bidirectional"))
    )
    (net (code "131") (name "unconnected-(IC12-~{FAULT}-Pad3)") (class "Default")
      (node (ref "IC12") (pin "3") (pinfunction "~{FAULT}_3") (pintype "bidirectional"))
    )
    (net (code "132") (name "unconnected-(IC16-ADJ{slash}SENSE-Pad10)") (class "Default")
      (node (ref "IC16") (pin "10") (pinfunction "ADJ/SENSE_10") (pintype "bidirectional"))
    )
    (net (code "133") (name "unconnected-(IC16-EP-Pad13)") (class "Default")
      (node (ref "IC16") (pin "13") (pinfunction "EP_13") (pintype "bidirectional"))
    )
    (net (code "134") (name "unconnected-(IC16-GND{slash}ADJ-Pad9)") (class "Default")
      (node (ref "IC16") (pin "9") (pinfunction "GND/ADJ_9") (pintype "bidirectional"))
    )
    (net (code "135") (name "unconnected-(IC16-IMAX-Pad5)") (class "Default")
      (node (ref "IC16") (pin "5") (pinfunction "IMAX_5") (pintype "bidirectional"))
    )
    (net (code "136") (name "unconnected-(IC16-NC_1-Pad6)") (class "Default")
      (node (ref "IC16") (pin "6") (pinfunction "NC_1_6") (pintype "bidirectional"))
    )
    (net (code "137") (name "unconnected-(IC16-NC_2-Pad7)") (class "Default")
      (node (ref "IC16") (pin "7") (pinfunction "NC_2_7") (pintype "bidirectional"))
    )
    (net (code "138") (name "unconnected-(IC16-PWRGD-Pad4)") (class "Default")
      (node (ref "IC16") (pin "4") (pinfunction "PWRGD_4") (pintype "bidirectional"))
    )
    (net (code "139") (name "unconnected-(IC16-REF{slash}BYP-Pad8)") (class "Default")
      (node (ref "IC16") (pin "8") (pinfunction "REF/BYP_8") (pintype "bidirectional"))
    )
    (net (code "140") (name "unconnected-(IC16-~{SHDN}-Pad3)") (class "Default")
      (node (ref "IC16") (pin "3") (pinfunction "~{SHDN}_3") (pintype "bidirectional"))
    )
    (net (code "141") (name "unconnected-(LI_ION_BATTERY_PACK-+-Pad+@1)") (class "Default")
      (node (ref "LI_ION_BATTERY_PACK") (pin "+@1") (pinfunction "+_+@1") (pintype "passive"))
    )
  )
)
